# SHDN-S08-V00-PSU.net
KiCad netlist of a schematic drawn in Altium Designer
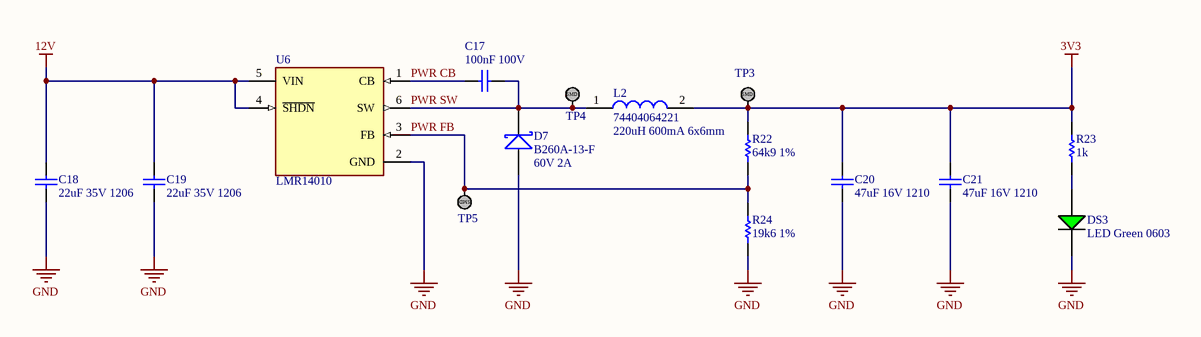
[diagram p0: SHDN-S08-V00-PSU.SchDoc]

(export (version "E")
  (design (tool "Eeschema 10.0.6"))
  (components
    (comp (ref "C17")
      (value "100nF 100V")
      (footprint "Cap_Ceramic_0603")
      (description "Capacitor, Ceramic, SMD, 100nF, 100V, 5%, X7R, 0603")
      (libsource (lib "StandardCapacitors") (part "100nF 100V 5% X7R 0603"))
    )
    (comp (ref "C18")
      (value "22uF 35V 1206")
      (footprint "Cap_Ceramic_1206")
      (description "Capacitor, Ceramic, SMD, 22uF, 35V, 10%, X7R, 1206")
      (libsource (lib "StandardCapacitors") (part "22uF 35V 10% X7R 1206"))
    )
    (comp (ref "C19")
      (value "22uF 35V 1206")
      (footprint "Cap_Ceramic_1206")
      (description "Capacitor, Ceramic, SMD, 22uF, 35V, 10%, X7R, 1206")
      (libsource (lib "StandardCapacitors") (part "22uF 35V 10% X7R 1206"))
    )
    (comp (ref "C20")
      (value "47uF 16V 1210")
      (footprint "Cap_Ceramic_1210")
      (description "Capacitor, Ceramic, SMD, 47uF, 16V, 5%, X7R, 1210")
      (libsource (lib "StandardCapacitors") (part "47uF 16V 10% X7R 1210"))
    )
    (comp (ref "C21")
      (value "47uF 16V 1210")
      (footprint "Cap_Ceramic_1210")
      (description "Capacitor, Ceramic, SMD, 47uF, 16V, 5%, X7R, 1210")
      (libsource (lib "StandardCapacitors") (part "47uF 16V 10% X7R 1210"))
    )
    (comp (ref "D7")
      (value "B260A-13-F")
      (footprint "SMA")
      (description "Diode, Schottky Barrier Rectifier, 60 V, 2 A, B260A-13-F")
      (libsource (lib "QUTMS_DiodeLibrary") (part "B260A-13-F"))
    )
    (comp (ref "DS3")
      (value "LED Green 0603")
      (footprint "LED GREEN 0603")
      (libsource (lib "QUTMS_LEDLibrary") (part "LED Green 0603"))
    )
    (comp (ref "L2")
      (value "74404064221")
      (footprint "Inductor_6x6mm")
      (description "FIXED IND 220UH 660MA 850 MOHM")
      (libsource (lib "QUTMS_InductorLibrary") (part "74404064221"))
    )
    (comp (ref "R22")
      (value "64k9 1%")
      (footprint "Res_ThinFilm_0603")
      (description "Resistor, SMD, 64k9, 0.1W, 5%, 0603")
      (libsource (lib "StandardResistors") (part "64k9 1% 0603"))
    )
    (comp (ref "R23")
      (value "1k")
      (footprint "Res_ThinFilm_0603")
      (description "Resistor, SMD, 1k, 0.1W, 5%, 0603")
      (libsource (lib "StandardResistors") (part "1k 5% 0603"))
    )
    (comp (ref "R24")
      (value "19k6 1%")
      (footprint "Res_ThinFilm_0603")
      (description "Resistor, SMD, 19k6, 0.1W, 5%, 0603")
      (libsource (lib "StandardResistors") (part "19k6 1% 0603"))
    )
    (comp (ref "TP3")
      (value "TestPoint_SMD")
      (footprint "TestPointSMD")
      (libsource (lib "StandardTest") (part "TestPoint_SMD"))
    )
    (comp (ref "TP4")
      (value "TestPoint_SMD")
      (footprint "TestPointSMD")
      (libsource (lib "StandardTest") (part "TestPoint_SMD"))
    )
    (comp (ref "TP5")
      (value "TestPoint_SMD")
      (footprint "TestPointSMD")
      (libsource (lib "StandardTest") (part "TestPoint_SMD"))
    )
    (comp (ref "U6")
      (value "LMR14010")
      (footprint "LMR14010")
      (libsource (lib "QUTMS_PowerSupplyLibrary") (part "LMR14010"))
    )
  )
  (nets
    (net (code "1") (name "/PWR CB") (class "Default")
      (node (ref "C17") (pin "1") (pinfunction "1_1") (pintype "passive"))
      (node (ref "U6") (pin "1") (pinfunction "CB_1") (pintype "input"))
    )
    (net (code "2") (name "/PWR FB") (class "Default")
      (node (ref "R22") (pin "1") (pinfunction "1_1") (pintype "passive"))
      (node (ref "R24") (pin "2") (pinfunction "2_2") (pintype "passive"))
      (node (ref "TP5") (pin "1") (pinfunction "1_1") (pintype "passive"))
      (node (ref "U6") (pin "3") (pinfunction "FB_3") (pintype "input"))
    )
    (net (code "3") (name "/PWR SW") (class "Default")
      (node (ref "C17") (pin "2") (pinfunction "2_2") (pintype "passive"))
      (node (ref "D7") (pin "K") (pinfunction "K_K") (pintype "passive"))
      (node (ref "L2") (pin "1") (pinfunction "1_1") (pintype "passive"))
      (node (ref "TP4") (pin "1") (pinfunction "1_1") (pintype "passive"))
      (node (ref "U6") (pin "6") (pinfunction "SW_6") (pintype "output"))
    )
    (net (code "4") (name "3V3") (class "Default")
      (node (ref "C20") (pin "2") (pinfunction "2_2") (pintype "passive"))
      (node (ref "C21") (pin "2") (pinfunction "2_2") (pintype "passive"))
      (node (ref "L2") (pin "2") (pinfunction "2_2") (pintype "passive"))
      (node (ref "R22") (pin "2") (pinfunction "2_2") (pintype "passive"))
      (node (ref "R23") (pin "2") (pinfunction "2_2") (pintype "passive"))
      (node (ref "TP3") (pin "1") (pinfunction "1_1") (pintype "passive"))
    )
    (net (code "5") (name "12V") (class "Default")
      (node (ref "C18") (pin "2") (pinfunction "2_2") (pintype "passive"))
      (node (ref "C19") (pin "2") (pinfunction "2_2") (pintype "passive"))
      (node (ref "U6") (pin "4") (pinfunction "~{SHDN}_4") (pintype "input"))
      (node (ref "U6") (pin "5") (pinfunction "VIN_5") (pintype "power_in"))
    )
    (net (code "6") (name "GND") (class "Default")
      (node (ref "C18") (pin "1") (pinfunction "1_1") (pintype "passive"))
      (node (ref "C19") (pin "1") (pinfunction "1_1") (pintype "passive"))
      (node (ref "C20") (pin "1") (pinfunction "1_1") (pintype "passive"))
      (node (ref "C21") (pin "1") (pinfunction "1_1") (pintype "passive"))
      (node (ref "D7") (pin "A") (pinfunction "A_A") (pintype "passive"))
      (node (ref "DS3") (pin "2") (pinfunction "C_2") (pintype "passive"))
      (node (ref "R24") (pin "1") (pinfunction "1_1") (pintype "passive"))
      (node (ref "U6") (pin "2") (pinfunction "GND_2") (pintype "power_in"))
    )
    (net (code "7") (name "Net-(DS3-A)") (class "Default")
      (node (ref "DS3") (pin "1") (pinfunction "A_1") (pintype "passive"))
      (node (ref "R23") (pin "1") (pinfunction "1_1") (pintype "passive"))
    )
  )
)
